# pressure.net
KiCad netlist of a schematic drawn in Altium Designer
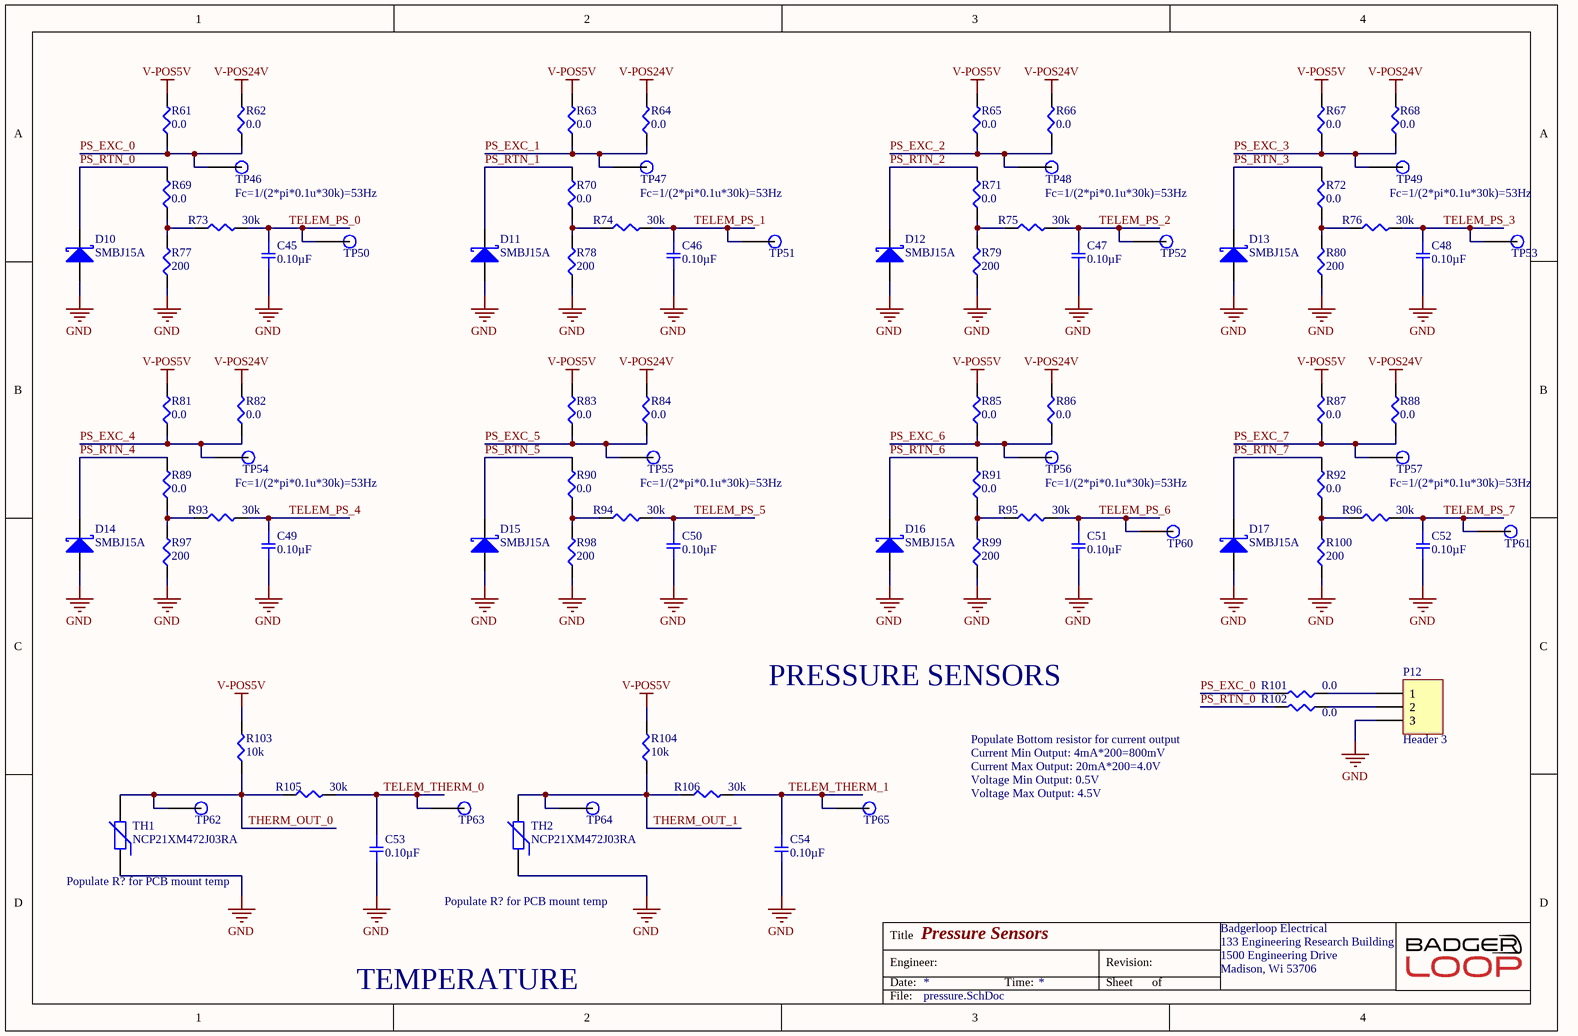
[diagram p0: pressure.SchDoc]

(export (version "E")
  (design (tool "Eeschema 10.0.6"))
  (components
    (comp (ref "C45")
      (value "0.10µF")
      (footprint "SMD-0805C")
      (description "CAP CER 0.1UF 25V X7R 0805")
      (fields
        (field (name "DIGI-KEY PART NUMBER") "490-12754-1-ND")
        (field (name "PART NUMBER") "GRM219R71E104KA01D")
      )
      (libsource (lib "capacitors") (part "GRM219R71E104KA01D"))
    )
    (comp (ref "C46")
      (value "0.10µF")
      (footprint "SMD-0805C")
      (description "CAP CER 0.1UF 25V X7R 0805")
      (fields
        (field (name "DIGI-KEY PART NUMBER") "490-12754-1-ND")
        (field (name "PART NUMBER") "GRM219R71E104KA01D")
      )
      (libsource (lib "capacitors") (part "GRM219R71E104KA01D"))
    )
    (comp (ref "C47")
      (value "0.10µF")
      (footprint "SMD-0805C")
      (description "CAP CER 0.1UF 25V X7R 0805")
      (fields
        (field (name "DIGI-KEY PART NUMBER") "490-12754-1-ND")
        (field (name "PART NUMBER") "GRM219R71E104KA01D")
      )
      (libsource (lib "capacitors") (part "GRM219R71E104KA01D"))
    )
    (comp (ref "C48")
      (value "0.10µF")
      (footprint "SMD-0805C")
      (description "CAP CER 0.1UF 25V X7R 0805")
      (fields
        (field (name "DIGI-KEY PART NUMBER") "490-12754-1-ND")
        (field (name "PART NUMBER") "GRM219R71E104KA01D")
      )
      (libsource (lib "capacitors") (part "GRM219R71E104KA01D"))
    )
    (comp (ref "C49")
      (value "0.10µF")
      (footprint "SMD-0805C")
      (description "CAP CER 0.1UF 25V X7R 0805")
      (fields
        (field (name "DIGI-KEY PART NUMBER") "490-12754-1-ND")
        (field (name "PART NUMBER") "GRM219R71E104KA01D")
      )
      (libsource (lib "capacitors") (part "GRM219R71E104KA01D"))
    )
    (comp (ref "C50")
      (value "0.10µF")
      (footprint "SMD-0805C")
      (description "CAP CER 0.1UF 25V X7R 0805")
      (fields
        (field (name "DIGI-KEY PART NUMBER") "490-12754-1-ND")
        (field (name "PART NUMBER") "GRM219R71E104KA01D")
      )
      (libsource (lib "capacitors") (part "GRM219R71E104KA01D"))
    )
    (comp (ref "C51")
      (value "0.10µF")
      (footprint "SMD-0805C")
      (description "CAP CER 0.1UF 25V X7R 0805")
      (fields
        (field (name "DIGI-KEY PART NUMBER") "490-12754-1-ND")
        (field (name "PART NUMBER") "GRM219R71E104KA01D")
      )
      (libsource (lib "capacitors") (part "GRM219R71E104KA01D"))
    )
    (comp (ref "C52")
      (value "0.10µF")
      (footprint "SMD-0805C")
      (description "CAP CER 0.1UF 25V X7R 0805")
      (fields
        (field (name "DIGI-KEY PART NUMBER") "490-12754-1-ND")
        (field (name "PART NUMBER") "GRM219R71E104KA01D")
      )
      (libsource (lib "capacitors") (part "GRM219R71E104KA01D"))
    )
    (comp (ref "C53")
      (value "0.10µF")
      (footprint "SMD-0805C")
      (description "CAP CER 0.1UF 16V X7R 0805")
      (fields
        (field (name "DIGI-KEY PART NUMBER") "490-1683-1-ND")
        (field (name "PART NUMBER") "GRM219R71C104KA01D")
      )
      (libsource (lib "capacitors") (part "GRM219R71C104KA01D"))
    )
    (comp (ref "C54")
      (value "0.10µF")
      (footprint "SMD-0805C")
      (description "CAP CER 0.1UF 16V X7R 0805")
      (fields
        (field (name "DIGI-KEY PART NUMBER") "490-1683-1-ND")
        (field (name "PART NUMBER") "GRM219R71C104KA01D")
      )
      (libsource (lib "capacitors") (part "GRM219R71C104KA01D"))
    )
    (comp (ref "D10")
      (value "SMBJ15A")
      (footprint "DIOM4436X26N")
      (description "TVS DIODE 15V 24.4V DO214AA")
      (fields (field (name "MANUFACTURER") "Littelfuse") (field (name "VOLTAGE") "5V"))
      (libsource (lib "misc") (part "SMBJ15A"))
    )
    (comp (ref "D11")
      (value "SMBJ15A")
      (footprint "DIOM4436X26N")
      (description "TVS DIODE 15V 24.4V DO214AA")
      (fields (field (name "MANUFACTURER") "Littelfuse") (field (name "VOLTAGE") "5V"))
      (libsource (lib "misc") (part "SMBJ15A"))
    )
    (comp (ref "D12")
      (value "SMBJ15A")
      (footprint "DIOM4436X26N")
      (description "TVS DIODE 15V 24.4V DO214AA")
      (fields (field (name "MANUFACTURER") "Littelfuse") (field (name "VOLTAGE") "5V"))
      (libsource (lib "misc") (part "SMBJ15A"))
    )
    (comp (ref "D13")
      (value "SMBJ15A")
      (footprint "DIOM4436X26N")
      (description "TVS DIODE 15V 24.4V DO214AA")
      (fields (field (name "MANUFACTURER") "Littelfuse") (field (name "VOLTAGE") "5V"))
      (libsource (lib "misc") (part "SMBJ15A"))
    )
    (comp (ref "D14")
      (value "SMBJ15A")
      (footprint "DIOM4436X26N")
      (description "TVS DIODE 15V 24.4V DO214AA")
      (fields (field (name "MANUFACTURER") "Littelfuse") (field (name "VOLTAGE") "5V"))
      (libsource (lib "misc") (part "SMBJ15A"))
    )
    (comp (ref "D15")
      (value "SMBJ15A")
      (footprint "DIOM4436X26N")
      (description "TVS DIODE 15V 24.4V DO214AA")
      (fields (field (name "MANUFACTURER") "Littelfuse") (field (name "VOLTAGE") "5V"))
      (libsource (lib "misc") (part "SMBJ15A"))
    )
    (comp (ref "D16")
      (value "SMBJ15A")
      (footprint "DIOM4436X26N")
      (description "TVS DIODE 15V 24.4V DO214AA")
      (fields (field (name "MANUFACTURER") "Littelfuse") (field (name "VOLTAGE") "5V"))
      (libsource (lib "misc") (part "SMBJ15A"))
    )
    (comp (ref "D17")
      (value "SMBJ15A")
      (footprint "DIOM4436X26N")
      (description "TVS DIODE 15V 24.4V DO214AA")
      (fields (field (name "MANUFACTURER") "Littelfuse") (field (name "VOLTAGE") "5V"))
      (libsource (lib "misc") (part "SMBJ15A"))
    )
    (comp (ref "P12")
      (value "Header 3")
      (footprint "Pin Header 1x3 TH Pitch 2.54mm")
      (description "Header, 3-Pin")
      (fields (field (name "PUBLISHER") "Altium Limited"))
      (libsource (lib "connector") (part "Header 3"))
    )
    (comp (ref "R61")
      (value "0.0")
      (footprint "SMD-0805-RES")
      (description "RES SMD 0.0 OHM JUMPER 1/8W 0805")
      (fields (field (name "PART NUMBER") "ERJ-6GEY0R00V") (field (name "DIGI-KEY PART NUMBER") "P0.0ACT-ND"))
      (libsource (lib "resistors") (part "ERJ-6GEY0R00V"))
    )
    (comp (ref "R62")
      (value "0.0")
      (footprint "SMD-0805-RES")
      (description "RES SMD 0.0 OHM JUMPER 1/8W 0805")
      (fields (field (name "PART NUMBER") "ERJ-6GEY0R00V") (field (name "DIGI-KEY PART NUMBER") "P0.0ACT-ND"))
      (libsource (lib "resistors") (part "ERJ-6GEY0R00V"))
    )
    (comp (ref "R63")
      (value "0.0")
      (footprint "SMD-0805-RES")
      (description "RES SMD 0.0 OHM JUMPER 1/8W 0805")
      (fields (field (name "PART NUMBER") "ERJ-6GEY0R00V") (field (name "DIGI-KEY PART NUMBER") "P0.0ACT-ND"))
      (libsource (lib "resistors") (part "ERJ-6GEY0R00V"))
    )
    (comp (ref "R64")
      (value "0.0")
      (footprint "SMD-0805-RES")
      (description "RES SMD 0.0 OHM JUMPER 1/8W 0805")
      (fields (field (name "PART NUMBER") "ERJ-6GEY0R00V") (field (name "DIGI-KEY PART NUMBER") "P0.0ACT-ND"))
      (libsource (lib "resistors") (part "ERJ-6GEY0R00V"))
    )
    (comp (ref "R65")
      (value "0.0")
      (footprint "SMD-0805-RES")
      (description "RES SMD 0.0 OHM JUMPER 1/8W 0805")
      (fields (field (name "PART NUMBER") "ERJ-6GEY0R00V") (field (name "DIGI-KEY PART NUMBER") "P0.0ACT-ND"))
      (libsource (lib "resistors") (part "ERJ-6GEY0R00V"))
    )
    (comp (ref "R66")
      (value "0.0")
      (footprint "SMD-0805-RES")
      (description "RES SMD 0.0 OHM JUMPER 1/8W 0805")
      (fields (field (name "PART NUMBER") "ERJ-6GEY0R00V") (field (name "DIGI-KEY PART NUMBER") "P0.0ACT-ND"))
      (libsource (lib "resistors") (part "ERJ-6GEY0R00V"))
    )
    (comp (ref "R67")
      (value "0.0")
      (footprint "SMD-0805-RES")
      (description "RES SMD 0.0 OHM JUMPER 1/8W 0805")
      (fields (field (name "PART NUMBER") "ERJ-6GEY0R00V") (field (name "DIGI-KEY PART NUMBER") "P0.0ACT-ND"))
      (libsource (lib "resistors") (part "ERJ-6GEY0R00V"))
    )
    (comp (ref "R68")
      (value "0.0")
      (footprint "SMD-0805-RES")
      (description "RES SMD 0.0 OHM JUMPER 1/8W 0805")
      (fields (field (name "PART NUMBER") "ERJ-6GEY0R00V") (field (name "DIGI-KEY PART NUMBER") "P0.0ACT-ND"))
      (libsource (lib "resistors") (part "ERJ-6GEY0R00V"))
    )
    (comp (ref "R69")
      (value "0.0")
      (footprint "SMD-0805-RES")
      (description "RES SMD 0.0 OHM JUMPER 1/8W 0805")
      (fields (field (name "PART NUMBER") "ERJ-6GEY0R00V") (field (name "DIGI-KEY PART NUMBER") "P0.0ACT-ND"))
      (libsource (lib "resistors") (part "ERJ-6GEY0R00V"))
    )
    (comp (ref "R70")
      (value "0.0")
      (footprint "SMD-0805-RES")
      (description "RES SMD 0.0 OHM JUMPER 1/8W 0805")
      (fields (field (name "PART NUMBER") "ERJ-6GEY0R00V") (field (name "DIGI-KEY PART NUMBER") "P0.0ACT-ND"))
      (libsource (lib "resistors") (part "ERJ-6GEY0R00V"))
    )
    (comp (ref "R71")
      (value "0.0")
      (footprint "SMD-0805-RES")
      (description "RES SMD 0.0 OHM JUMPER 1/8W 0805")
      (fields (field (name "PART NUMBER") "ERJ-6GEY0R00V") (field (name "DIGI-KEY PART NUMBER") "P0.0ACT-ND"))
      (libsource (lib "resistors") (part "ERJ-6GEY0R00V"))
    )
    (comp (ref "R72")
      (value "0.0")
      (footprint "SMD-0805-RES")
      (description "RES SMD 0.0 OHM JUMPER 1/8W 0805")
      (fields (field (name "PART NUMBER") "ERJ-6GEY0R00V") (field (name "DIGI-KEY PART NUMBER") "P0.0ACT-ND"))
      (libsource (lib "resistors") (part "ERJ-6GEY0R00V"))
    )
    (comp (ref "R73")
      (value "30k")
      (footprint "SMD-0805-RES")
      (description "RES SMD 30K OHM 1% 1/8W 0805")
      (fields
        (field (name "PART NUMBER") "ERJ-6ENF3002V")
        (field (name "DIGI-KEY PART NUMBER") "P30.0KCCT-ND")
      )
      (libsource (lib "resistors") (part "ERJ-6ENF3002V"))
    )
    (comp (ref "R74")
      (value "30k")
      (footprint "SMD-0805-RES")
      (description "RES SMD 30K OHM 1% 1/8W 0805")
      (fields
        (field (name "PART NUMBER") "ERJ-6ENF3002V")
        (field (name "DIGI-KEY PART NUMBER") "P30.0KCCT-ND")
      )
      (libsource (lib "resistors") (part "ERJ-6ENF3002V"))
    )
    (comp (ref "R75")
      (value "30k")
      (footprint "SMD-0805-RES")
      (description "RES SMD 30K OHM 1% 1/8W 0805")
      (fields
        (field (name "PART NUMBER") "ERJ-6ENF3002V")
        (field (name "DIGI-KEY PART NUMBER") "P30.0KCCT-ND")
      )
      (libsource (lib "resistors") (part "ERJ-6ENF3002V"))
    )
    (comp (ref "R76")
      (value "30k")
      (footprint "SMD-0805-RES")
      (description "RES SMD 30K OHM 1% 1/8W 0805")
      (fields
        (field (name "PART NUMBER") "ERJ-6ENF3002V")
        (field (name "DIGI-KEY PART NUMBER") "P30.0KCCT-ND")
      )
      (libsource (lib "resistors") (part "ERJ-6ENF3002V"))
    )
    (comp (ref "R77")
      (value "200")
      (footprint "SMD-0805-RES")
      (description "RES SMD 200 OHM 1% 1/2W 0805")
      (fields
        (field (name "PART NUMBER") "ERJ-P06F2000V")
        (field (name "DIGI-KEY PART NUMBER") "P16064CT-ND")
      )
      (libsource (lib "resistors") (part "ERJ-P06F2000V"))
    )
    (comp (ref "R78")
      (value "200")
      (footprint "SMD-0805-RES")
      (description "RES SMD 200 OHM 1% 1/2W 0805")
      (fields
        (field (name "PART NUMBER") "ERJ-P06F2000V")
        (field (name "DIGI-KEY PART NUMBER") "P16064CT-ND")
      )
      (libsource (lib "resistors") (part "ERJ-P06F2000V"))
    )
    (comp (ref "R79")
      (value "200")
      (footprint "SMD-0805-RES")
      (description "RES SMD 200 OHM 1% 1/2W 0805")
      (fields
        (field (name "PART NUMBER") "ERJ-P06F2000V")
        (field (name "DIGI-KEY PART NUMBER") "P16064CT-ND")
      )
      (libsource (lib "resistors") (part "ERJ-P06F2000V"))
    )
    (comp (ref "R80")
      (value "200")
      (footprint "SMD-0805-RES")
      (description "RES SMD 200 OHM 1% 1/2W 0805")
      (fields
        (field (name "PART NUMBER") "ERJ-P06F2000V")
        (field (name "DIGI-KEY PART NUMBER") "P16064CT-ND")
      )
      (libsource (lib "resistors") (part "ERJ-P06F2000V"))
    )
    (comp (ref "R81")
      (value "0.0")
      (footprint "SMD-0805-RES")
      (description "RES SMD 0.0 OHM JUMPER 1/8W 0805")
      (fields (field (name "PART NUMBER") "ERJ-6GEY0R00V") (field (name "DIGI-KEY PART NUMBER") "P0.0ACT-ND"))
      (libsource (lib "resistors") (part "ERJ-6GEY0R00V"))
    )
    (comp (ref "R82")
      (value "0.0")
      (footprint "SMD-0805-RES")
      (description "RES SMD 0.0 OHM JUMPER 1/8W 0805")
      (fields (field (name "PART NUMBER") "ERJ-6GEY0R00V") (field (name "DIGI-KEY PART NUMBER") "P0.0ACT-ND"))
      (libsource (lib "resistors") (part "ERJ-6GEY0R00V"))
    )
    (comp (ref "R83")
      (value "0.0")
      (footprint "SMD-0805-RES")
      (description "RES SMD 0.0 OHM JUMPER 1/8W 0805")
      (fields (field (name "PART NUMBER") "ERJ-6GEY0R00V") (field (name "DIGI-KEY PART NUMBER") "P0.0ACT-ND"))
      (libsource (lib "resistors") (part "ERJ-6GEY0R00V"))
    )
    (comp (ref "R84")
      (value "0.0")
      (footprint "SMD-0805-RES")
      (description "RES SMD 0.0 OHM JUMPER 1/8W 0805")
      (fields (field (name "PART NUMBER") "ERJ-6GEY0R00V") (field (name "DIGI-KEY PART NUMBER") "P0.0ACT-ND"))
      (libsource (lib "resistors") (part "ERJ-6GEY0R00V"))
    )
    (comp (ref "R85")
      (value "0.0")
      (footprint "SMD-0805-RES")
      (description "RES SMD 0.0 OHM JUMPER 1/8W 0805")
      (fields (field (name "PART NUMBER") "ERJ-6GEY0R00V") (field (name "DIGI-KEY PART NUMBER") "P0.0ACT-ND"))
      (libsource (lib "resistors") (part "ERJ-6GEY0R00V"))
    )
    (comp (ref "R86")
      (value "0.0")
      (footprint "SMD-0805-RES")
      (description "RES SMD 0.0 OHM JUMPER 1/8W 0805")
      (fields (field (name "PART NUMBER") "ERJ-6GEY0R00V") (field (name "DIGI-KEY PART NUMBER") "P0.0ACT-ND"))
      (libsource (lib "resistors") (part "ERJ-6GEY0R00V"))
    )
    (comp (ref "R87")
      (value "0.0")
      (footprint "SMD-0805-RES")
      (description "RES SMD 0.0 OHM JUMPER 1/8W 0805")
      (fields (field (name "PART NUMBER") "ERJ-6GEY0R00V") (field (name "DIGI-KEY PART NUMBER") "P0.0ACT-ND"))
      (libsource (lib "resistors") (part "ERJ-6GEY0R00V"))
    )
    (comp (ref "R88")
      (value "0.0")
      (footprint "SMD-0805-RES")
      (description "RES SMD 0.0 OHM JUMPER 1/8W 0805")
      (fields (field (name "PART NUMBER") "ERJ-6GEY0R00V") (field (name "DIGI-KEY PART NUMBER") "P0.0ACT-ND"))
      (libsource (lib "resistors") (part "ERJ-6GEY0R00V"))
    )
    (comp (ref "R89")
      (value "0.0")
      (footprint "SMD-0805-RES")
      (description "RES SMD 0.0 OHM JUMPER 1/8W 0805")
      (fields (field (name "PART NUMBER") "ERJ-6GEY0R00V") (field (name "DIGI-KEY PART NUMBER") "P0.0ACT-ND"))
      (libsource (lib "resistors") (part "ERJ-6GEY0R00V"))
    )
    (comp (ref "R90")
      (value "0.0")
      (footprint "SMD-0805-RES")
      (description "RES SMD 0.0 OHM JUMPER 1/8W 0805")
      (fields (field (name "PART NUMBER") "ERJ-6GEY0R00V") (field (name "DIGI-KEY PART NUMBER") "P0.0ACT-ND"))
      (libsource (lib "resistors") (part "ERJ-6GEY0R00V"))
    )
    (comp (ref "R91")
      (value "0.0")
      (footprint "SMD-0805-RES")
      (description "RES SMD 0.0 OHM JUMPER 1/8W 0805")
      (fields (field (name "PART NUMBER") "ERJ-6GEY0R00V") (field (name "DIGI-KEY PART NUMBER") "P0.0ACT-ND"))
      (libsource (lib "resistors") (part "ERJ-6GEY0R00V"))
    )
    (comp (ref "R92")
      (value "0.0")
      (footprint "SMD-0805-RES")
      (description "RES SMD 0.0 OHM JUMPER 1/8W 0805")
      (fields (field (name "PART NUMBER") "ERJ-6GEY0R00V") (field (name "DIGI-KEY PART NUMBER") "P0.0ACT-ND"))
      (libsource (lib "resistors") (part "ERJ-6GEY0R00V"))
    )
    (comp (ref "R93")
      (value "30k")
      (footprint "SMD-0805-RES")
      (description "RES SMD 30K OHM 1% 1/8W 0805")
      (fields
        (field (name "PART NUMBER") "ERJ-6ENF3002V")
        (field (name "DIGI-KEY PART NUMBER") "P30.0KCCT-ND")
      )
      (libsource (lib "resistors") (part "ERJ-6ENF3002V"))
    )
    (comp (ref "R94")
      (value "30k")
      (footprint "SMD-0805-RES")
      (description "RES SMD 30K OHM 1% 1/8W 0805")
      (fields
        (field (name "PART NUMBER") "ERJ-6ENF3002V")
        (field (name "DIGI-KEY PART NUMBER") "P30.0KCCT-ND")
      )
      (libsource (lib "resistors") (part "ERJ-6ENF3002V"))
    )
    (comp (ref "R95")
      (value "30k")
      (footprint "SMD-0805-RES")
      (description "RES SMD 30K OHM 1% 1/8W 0805")
      (fields
        (field (name "PART NUMBER") "ERJ-6ENF3002V")
        (field (name "DIGI-KEY PART NUMBER") "P30.0KCCT-ND")
      )
      (libsource (lib "resistors") (part "ERJ-6ENF3002V"))
    )
    (comp (ref "R96")
      (value "30k")
      (footprint "SMD-0805-RES")
      (description "RES SMD 30K OHM 1% 1/8W 0805")
      (fields
        (field (name "PART NUMBER") "ERJ-6ENF3002V")
        (field (name "DIGI-KEY PART NUMBER") "P30.0KCCT-ND")
      )
      (libsource (lib "resistors") (part "ERJ-6ENF3002V"))
    )
    (comp (ref "R97")
      (value "200")
      (footprint "SMD-0805-RES")
      (description "RES SMD 200 OHM 1% 1/2W 0805")
      (fields
        (field (name "PART NUMBER") "ERJ-P06F2000V")
        (field (name "DIGI-KEY PART NUMBER") "P16064CT-ND")
      )
      (libsource (lib "resistors") (part "ERJ-P06F2000V"))
    )
    (comp (ref "R98")
      (value "200")
      (footprint "SMD-0805-RES")
      (description "RES SMD 200 OHM 1% 1/2W 0805")
      (fields
        (field (name "PART NUMBER") "ERJ-P06F2000V")
        (field (name "DIGI-KEY PART NUMBER") "P16064CT-ND")
      )
      (libsource (lib "resistors") (part "ERJ-P06F2000V"))
    )
    (comp (ref "R99")
      (value "200")
      (footprint "SMD-0805-RES")
      (description "RES SMD 200 OHM 1% 1/2W 0805")
      (fields
        (field (name "PART NUMBER") "ERJ-P06F2000V")
        (field (name "DIGI-KEY PART NUMBER") "P16064CT-ND")
      )
      (libsource (lib "resistors") (part "ERJ-P06F2000V"))
    )
    (comp (ref "R100")
      (value "200")
      (footprint "SMD-0805-RES")
      (description "RES SMD 200 OHM 1% 1/2W 0805")
      (fields
        (field (name "PART NUMBER") "ERJ-P06F2000V")
        (field (name "DIGI-KEY PART NUMBER") "P16064CT-ND")
      )
      (libsource (lib "resistors") (part "ERJ-P06F2000V"))
    )
    (comp (ref "R101")
      (value "0.0")
      (footprint "SMD-0805-RES")
      (description "RES SMD 0.0 OHM JUMPER 1/8W 0805")
      (fields (field (name "PART NUMBER") "ERJ-6GEY0R00V") (field (name "DIGI-KEY PART NUMBER") "P0.0ACT-ND"))
      (libsource (lib "resistors") (part "ERJ-6GEY0R00V"))
    )
    (comp (ref "R102")
      (value "0.0")
      (footprint "SMD-0805-RES")
      (description "RES SMD 0.0 OHM JUMPER 1/8W 0805")
      (fields (field (name "PART NUMBER") "ERJ-6GEY0R00V") (field (name "DIGI-KEY PART NUMBER") "P0.0ACT-ND"))
      (libsource (lib "resistors") (part "ERJ-6GEY0R00V"))
    )
    (comp (ref "R103")
      (value "10k")
      (footprint "SMD-0805-RES")
      (description "RES SMD 10K OHM 1% 1/2W 0805")
      (fields
        (field (name "PART NUMBER") "ERJ-P06F1002V")
        (field (name "DIGI-KEY PART NUMBER") "P16059CT-ND")
      )
      (libsource (lib "resistors") (part "ERJ-P06F1002V"))
    )
    (comp (ref "R104")
      (value "10k")
      (footprint "SMD-0805-RES")
      (description "RES SMD 10K OHM 1% 1/2W 0805")
      (fields
        (field (name "PART NUMBER") "ERJ-P06F1002V")
        (field (name "DIGI-KEY PART NUMBER") "P16059CT-ND")
      )
      (libsource (lib "resistors") (part "ERJ-P06F1002V"))
    )
    (comp (ref "R105")
      (value "30k")
      (footprint "SMD-0805-RES")
      (description "RES SMD 30K OHM 1% 1/8W 0805")
      (fields
        (field (name "PART NUMBER") "ERJ-6ENF3002V")
        (field (name "DIGI-KEY PART NUMBER") "P30.0KCCT-ND")
      )
      (libsource (lib "resistors") (part "ERJ-6ENF3002V"))
    )
    (comp (ref "R106")
      (value "30k")
      (footprint "SMD-0805-RES")
      (description "RES SMD 30K OHM 1% 1/8W 0805")
      (fields
        (field (name "PART NUMBER") "ERJ-6ENF3002V")
        (field (name "DIGI-KEY PART NUMBER") "P30.0KCCT-ND")
      )
      (libsource (lib "resistors") (part "ERJ-6ENF3002V"))
    )
    (comp (ref "TH1")
      (value "NCP21XM472J03RA")
      (footprint "SMD-0805-RES")
      (description "NTC THERMISTOR 4.7K OHM 5% 0805")
      (fields (field (name "MANUFACTURER") "Murata") (field (name "TOLERANCE") "5%"))
      (libsource (lib "misc") (part "NCP21XM472J03RA"))
    )
    (comp (ref "TH2")
      (value "NCP21XM472J03RA")
      (footprint "SMD-0805-RES")
      (description "NTC THERMISTOR 4.7K OHM 5% 0805")
      (fields (field (name "MANUFACTURER") "Murata") (field (name "TOLERANCE") "5%"))
      (libsource (lib "misc") (part "NCP21XM472J03RA"))
    )
    (comp (ref "TP46")
      (value "TP")
      (footprint "Test Point")
      (description "SMD TEST POINT")
      (libsource (lib "misc") (part "TP"))
    )
    (comp (ref "TP47")
      (value "TP")
      (footprint "Test Point")
      (description "SMD TEST POINT")
      (libsource (lib "misc") (part "TP"))
    )
    (comp (ref "TP48")
      (value "TP")
      (footprint "Test Point")
      (description "SMD TEST POINT")
      (libsource (lib "misc") (part "TP"))
    )
    (comp (ref "TP49")
      (value "TP")
      (footprint "Test Point")
      (description "SMD TEST POINT")
      (libsource (lib "misc") (part "TP"))
    )
    (comp (ref "TP50")
      (value "TP")
      (footprint "Test Point")
      (description "SMD TEST POINT")
      (libsource (lib "misc") (part "TP"))
    )
    (comp (ref "TP51")
      (value "TP")
      (footprint "Test Point")
      (description "SMD TEST POINT")
      (libsource (lib "misc") (part "TP"))
    )
    (comp (ref "TP52")
      (value "TP")
      (footprint "Test Point")
      (description "SMD TEST POINT")
      (libsource (lib "misc") (part "TP"))
    )
    (comp (ref "TP53")
      (value "TP")
      (footprint "Test Point")
      (description "SMD TEST POINT")
      (libsource (lib "misc") (part "TP"))
    )
    (comp (ref "TP54")
      (value "TP")
      (footprint "Test Point")
      (description "SMD TEST POINT")
      (libsource (lib "misc") (part "TP"))
    )
    (comp (ref "TP55")
      (value "TP")
      (footprint "Test Point")
      (description "SMD TEST POINT")
      (libsource (lib "misc") (part "TP"))
    )
    (comp (ref "TP56")
      (value "TP")
      (footprint "Test Point")
      (description "SMD TEST POINT")
      (libsource (lib "misc") (part "TP"))
    )
    (comp (ref "TP57")
      (value "TP")
      (footprint "Test Point")
      (description "SMD TEST POINT")
      (libsource (lib "misc") (part "TP"))
    )
    (comp (ref "TP60")
      (value "TP")
      (footprint "Test Point")
      (description "SMD TEST POINT")
      (libsource (lib "misc") (part "TP"))
    )
    (comp (ref "TP61")
      (value "TP")
      (footprint "Test Point")
      (description "SMD TEST POINT")
      (libsource (lib "misc") (part "TP"))
    )
    (comp (ref "TP62")
      (value "TP")
      (footprint "Test Point")
      (description "SMD TEST POINT")
      (libsource (lib "misc") (part "TP"))
    )
    (comp (ref "TP63")
      (value "TP")
      (footprint "Test Point")
      (description "SMD TEST POINT")
      (libsource (lib "misc") (part "TP"))
    )
    (comp (ref "TP64")
      (value "TP")
      (footprint "Test Point")
      (description "SMD TEST POINT")
      (libsource (lib "misc") (part "TP"))
    )
    (comp (ref "TP65")
      (value "TP")
      (footprint "Test Point")
      (description "SMD TEST POINT")
      (libsource (lib "misc") (part "TP"))
    )
  )
  (nets
    (net (code "1") (name "/PS_EXC_0") (class "Default")
      (node (ref "R101") (pin "2") (pinfunction "2_2") (pintype "passive"))
      (node (ref "R61") (pin "1") (pinfunction "1_1") (pintype "passive"))
      (node (ref "R62") (pin "1") (pinfunction "1_1") (pintype "passive"))
      (node (ref "TP46") (pin "1") (pinfunction "1_1") (pintype "passive"))
    )
    (net (code "2") (name "/PS_EXC_1") (class "Default")
      (node (ref "R63") (pin "1") (pinfunction "1_1") (pintype "passive"))
      (node (ref "R64") (pin "1") (pinfunction "1_1") (pintype "passive"))
      (node (ref "TP47") (pin "1") (pinfunction "1_1") (pintype "passive"))
    )
    (net (code "3") (name "/PS_EXC_2") (class "Default")
      (node (ref "R65") (pin "1") (pinfunction "1_1") (pintype "passive"))
      (node (ref "R66") (pin "1") (pinfunction "1_1") (pintype "passive"))
      (node (ref "TP48") (pin "1") (pinfunction "1_1") (pintype "passive"))
    )
    (net (code "4") (name "/PS_EXC_3") (class "Default")
      (node (ref "R67") (pin "1") (pinfunction "1_1") (pintype "passive"))
      (node (ref "R68") (pin "1") (pinfunction "1_1") (pintype "passive"))
      (node (ref "TP49") (pin "1") (pinfunction "1_1") (pintype "passive"))
    )
    (net (code "5") (name "/PS_EXC_4") (class "Default")
      (node (ref "R81") (pin "1") (pinfunction "1_1") (pintype "passive"))
      (node (ref "R82") (pin "1") (pinfunction "1_1") (pintype "passive"))
      (node (ref "TP54") (pin "1") (pinfunction "1_1") (pintype "passive"))
    )
    (net (code "6") (name "/PS_EXC_5") (class "Default")
      (node (ref "R83") (pin "1") (pinfunction "1_1") (pintype "passive"))
      (node (ref "R84") (pin "1") (pinfunction "1_1") (pintype "passive"))
      (node (ref "TP55") (pin "1") (pinfunction "1_1") (pintype "passive"))
    )
    (net (code "7") (name "/PS_EXC_6") (class "Default")
      (node (ref "R85") (pin "1") (pinfunction "1_1") (pintype "passive"))
      (node (ref "R86") (pin "1") (pinfunction "1_1") (pintype "passive"))
      (node (ref "TP56") (pin "1") (pinfunction "1_1") (pintype "passive"))
    )
    (net (code "8") (name "/PS_EXC_7") (class "Default")
      (node (ref "R87") (pin "1") (pinfunction "1_1") (pintype "passive"))
      (node (ref "R88") (pin "1") (pinfunction "1_1") (pintype "passive"))
      (node (ref "TP57") (pin "1") (pinfunction "1_1") (pintype "passive"))
    )
    (net (code "9") (name "/PS_RTN_0") (class "Default")
      (node (ref "D10") (pin "1") (pinfunction "A_1") (pintype "passive"))
      (node (ref "R102") (pin "2") (pinfunction "2_2") (pintype "passive"))
      (node (ref "R69") (pin "2") (pinfunction "2_2") (pintype "passive"))
    )
    (net (code "10") (name "/PS_RTN_1") (class "Default")
      (node (ref "D11") (pin "1") (pinfunction "A_1") (pintype "passive"))
      (node (ref "R70") (pin "2") (pinfunction "2_2") (pintype "passive"))
    )
    (net (code "11") (name "/PS_RTN_2") (class "Default")
      (node (ref "D12") (pin "1") (pinfunction "A_1") (pintype "passive"))
      (node (ref "R71") (pin "2") (pinfunction "2_2") (pintype "passive"))
    )
    (net (code "12") (name "/PS_RTN_3") (class "Default")
      (node (ref "D13") (pin "1") (pinfunction "A_1") (pintype "passive"))
      (node (ref "R72") (pin "2") (pinfunction "2_2") (pintype "passive"))
    )
    (net (code "13") (name "/PS_RTN_4") (class "Default")
      (node (ref "D14") (pin "1") (pinfunction "A_1") (pintype "passive"))
      (node (ref "R89") (pin "2") (pinfunction "2_2") (pintype "passive"))
    )
    (net (code "14") (name "/PS_RTN_5") (class "Default")
      (node (ref "D15") (pin "1") (pinfunction "A_1") (pintype "passive"))
      (node (ref "R90") (pin "2") (pinfunction "2_2") (pintype "passive"))
    )
    (net (code "15") (name "/PS_RTN_6") (class "Default")
      (node (ref "D16") (pin "1") (pinfunction "A_1") (pintype "passive"))
      (node (ref "R91") (pin "2") (pinfunction "2_2") (pintype "passive"))
    )
    (net (code "16") (name "/PS_RTN_7") (class "Default")
      (node (ref "D17") (pin "1") (pinfunction "A_1") (pintype "passive"))
      (node (ref "R92") (pin "2") (pinfunction "2_2") (pintype "passive"))
    )
    (net (code "17") (name "/TELEM_PS_0") (class "Default")
      (node (ref "C45") (pin "1") (pinfunction "1_1") (pintype "passive"))
      (node (ref "R73") (pin "2") (pinfunction "2_2") (pintype "passive"))
      (node (ref "TP50") (pin "1") (pinfunction "1_1") (pintype "passive"))
    )
    (net (code "18") (name "/TELEM_PS_1") (class "Default")
      (node (ref "C46") (pin "1") (pinfunction "1_1") (pintype "passive"))
      (node (ref "R74") (pin "2") (pinfunction "2_2") (pintype "passive"))
      (node (ref "TP51") (pin "1") (pinfunction "1_1") (pintype "passive"))
    )
    (net (code "19") (name "/TELEM_PS_2") (class "Default")
      (node (ref "C47") (pin "1") (pinfunction "1_1") (pintype "passive"))
      (node (ref "R75") (pin "2") (pinfunction "2_2") (pintype "passive"))
      (node (ref "TP52") (pin "1") (pinfunction "1_1") (pintype "passive"))
    )
    (net (code "20") (name "/TELEM_PS_3") (class "Default")
      (node (ref "C48") (pin "1") (pinfunction "1_1") (pintype "passive"))
      (node (ref "R76") (pin "2") (pinfunction "2_2") (pintype "passive"))
      (node (ref "TP53") (pin "1") (pinfunction "1_1") (pintype "passive"))
    )
    (net (code "21") (name "/TELEM_PS_4") (class "Default")
      (node (ref "C49") (pin "1") (pinfunction "1_1") (pintype "passive"))
      (node (ref "R93") (pin "2") (pinfunction "2_2") (pintype "passive"))
    )
    (net (code "22") (name "/TELEM_PS_5") (class "Default")
      (node (ref "C50") (pin "1") (pinfunction "1_1") (pintype "passive"))
      (node (ref "R94") (pin "2") (pinfunction "2_2") (pintype "passive"))
    )
    (net (code "23") (name "/TELEM_PS_6") (class "Default")
      (node (ref "C51") (pin "1") (pinfunction "1_1") (pintype "passive"))
      (node (ref "R95") (pin "2") (pinfunction "2_2") (pintype "passive"))
      (node (ref "TP60") (pin "1") (pinfunction "1_1") (pintype "passive"))
    )
    (net (code "24") (name "/TELEM_PS_7") (class "Default")
      (node (ref "C52") (pin "1") (pinfunction "1_1") (pintype "passive"))
      (node (ref "R96") (pin "2") (pinfunction "2_2") (pintype "passive"))
      (node (ref "TP61") (pin "1") (pinfunction "1_1") (pintype "passive"))
    )
    (net (code "25") (name "/TELEM_THERM_0") (class "Default")
      (node (ref "C53") (pin "1") (pinfunction "1_1") (pintype "passive"))
      (node (ref "R105") (pin "2") (pinfunction "2_2") (pintype "passive"))
      (node (ref "TP63") (pin "1") (pinfunction "1_1") (pintype "passive"))
    )
    (net (code "26") (name "/TELEM_THERM_1") (class "Default")
      (node (ref "C54") (pin "1") (pinfunction "1_1") (pintype "passive"))
      (node (ref "R106") (pin "2") (pinfunction "2_2") (pintype "passive"))
      (node (ref "TP65") (pin "1") (pinfunction "1_1") (pintype "passive"))
    )
    (net (code "27") (name "/THERM_OUT_0") (class "Default")
      (node (ref "R103") (pin "1") (pinfunction "1_1") (pintype "passive"))
      (node (ref "R105") (pin "1") (pinfunction "1_1") (pintype "passive"))
      (node (ref "TH1") (pin "2") (pinfunction "2_2") (pintype "passive"))
      (node (ref "TP62") (pin "1") (pinfunction "1_1") (pintype "passive"))
    )
    (net (code "28") (name "/THERM_OUT_1") (class "Default")
      (node (ref "R104") (pin "1") (pinfunction "1_1") (pintype "passive"))
      (node (ref "R106") (pin "1") (pinfunction "1_1") (pintype "passive"))
      (node (ref "TH2") (pin "2") (pinfunction "2_2") (pintype "passive"))
      (node (ref "TP64") (pin "1") (pinfunction "1_1") (pintype "passive"))
    )
    (net (code "29") (name "GND") (class "Default")
      (node (ref "C45") (pin "2") (pinfunction "2_2") (pintype "passive"))
      (node (ref "C46") (pin "2") (pinfunction "2_2") (pintype "passive"))
      (node (ref "C47") (pin "2") (pinfunction "2_2") (pintype "passive"))
      (node (ref "C48") (pin "2") (pinfunction "2_2") (pintype "passive"))
      (node (ref "C49") (pin "2") (pinfunction "2_2") (pintype "passive"))
      (node (ref "C50") (pin "2") (pinfunction "2_2") (pintype "passive"))
      (node (ref "C51") (pin "2") (pinfunction "2_2") (pintype "passive"))
      (node (ref "C52") (pin "2") (pinfunction "2_2") (pintype "passive"))
      (node (ref "C53") (pin "2") (pinfunction "2_2") (pintype "passive"))
      (node (ref "C54") (pin "2") (pinfunction "2_2") (pintype "passive"))
      (node (ref "D10") (pin "2") (pinfunction "K_2") (pintype "passive"))
      (node (ref "D11") (pin "2") (pinfunction "K_2") (pintype "passive"))
      (node (ref "D12") (pin "2") (pinfunction "K_2") (pintype "passive"))
      (node (ref "D13") (pin "2") (pinfunction "K_2") (pintype "passive"))
      (node (ref "D14") (pin "2") (pinfunction "K_2") (pintype "passive"))
      (node (ref "D15") (pin "2") (pinfunction "K_2") (pintype "passive"))
      (node (ref "D16") (pin "2") (pinfunction "K_2") (pintype "passive"))
      (node (ref "D17") (pin "2") (pinfunction "K_2") (pintype "passive"))
      (node (ref "P12") (pin "3") (pinfunction "3_3") (pintype "passive"))
      (node (ref "R100") (pin "1") (pinfunction "1_1") (pintype "passive"))
      (node (ref "R77") (pin "1") (pinfunction "1_1") (pintype "passive"))
      (node (ref "R78") (pin "1") (pinfunction "1_1") (pintype "passive"))
      (node (ref "R79") (pin "1") (pinfunction "1_1") (pintype "passive"))
      (node (ref "R80") (pin "1") (pinfunction "1_1") (pintype "passive"))
      (node (ref "R97") (pin "1") (pinfunction "1_1") (pintype "passive"))
      (node (ref "R98") (pin "1") (pinfunction "1_1") (pintype "passive"))
      (node (ref "R99") (pin "1") (pinfunction "1_1") (pintype "passive"))
      (node (ref "TH1") (pin "1") (pinfunction "1_1") (pintype "passive"))
      (node (ref "TH2") (pin "1") (pinfunction "1_1") (pintype "passive"))
    )
    (net (code "30") (name "Net-(P12-Pad1)") (class "Default")
      (node (ref "P12") (pin "1") (pinfunction "1_1") (pintype "passive"))
      (node (ref "R101") (pin "1") (pinfunction "1_1") (pintype "passive"))
    )
    (net (code "31") (name "Net-(P12-Pad2)") (class "Default")
      (node (ref "P12") (pin "2") (pinfunction "2_2") (pintype "passive"))
      (node (ref "R102") (pin "1") (pinfunction "1_1") (pintype "passive"))
    )
    (net (code "32") (name "Net-(R69-Pad1)") (class "Default")
      (node (ref "R69") (pin "1") (pinfunction "1_1") (pintype "passive"))
      (node (ref "R73") (pin "1") (pinfunction "1_1") (pintype "passive"))
      (node (ref "R77") (pin "2") (pinfunction "2_2") (pintype "passive"))
    )
    (net (code "33") (name "Net-(R70-Pad1)") (class "Default")
      (node (ref "R70") (pin "1") (pinfunction "1_1") (pintype "passive"))
      (node (ref "R74") (pin "1") (pinfunction "1_1") (pintype "passive"))
      (node (ref "R78") (pin "2") (pinfunction "2_2") (pintype "passive"))
    )
    (net (code "34") (name "Net-(R71-Pad1)") (class "Default")
      (node (ref "R71") (pin "1") (pinfunction "1_1") (pintype "passive"))
      (node (ref "R75") (pin "1") (pinfunction "1_1") (pintype "passive"))
      (node (ref "R79") (pin "2") (pinfunction "2_2") (pintype "passive"))
    )
    (net (code "35") (name "Net-(R72-Pad1)") (class "Default")
      (node (ref "R72") (pin "1") (pinfunction "1_1") (pintype "passive"))
      (node (ref "R76") (pin "1") (pinfunction "1_1") (pintype "passive"))
      (node (ref "R80") (pin "2") (pinfunction "2_2") (pintype "passive"))
    )
    (net (code "36") (name "Net-(R89-Pad1)") (class "Default")
      (node (ref "R89") (pin "1") (pinfunction "1_1") (pintype "passive"))
      (node (ref "R93") (pin "1") (pinfunction "1_1") (pintype "passive"))
      (node (ref "R97") (pin "2") (pinfunction "2_2") (pintype "passive"))
    )
    (net (code "37") (name "Net-(R90-Pad1)") (class "Default")
      (node (ref "R90") (pin "1") (pinfunction "1_1") (pintype "passive"))
      (node (ref "R94") (pin "1") (pinfunction "1_1") (pintype "passive"))
      (node (ref "R98") (pin "2") (pinfunction "2_2") (pintype "passive"))
    )
    (net (code "38") (name "Net-(R91-Pad1)") (class "Default")
      (node (ref "R91") (pin "1") (pinfunction "1_1") (pintype "passive"))
      (node (ref "R95") (pin "1") (pinfunction "1_1") (pintype "passive"))
      (node (ref "R99") (pin "2") (pinfunction "2_2") (pintype "passive"))
    )
    (net (code "39") (name "Net-(R100-Pad2)") (class "Default")
      (node (ref "R100") (pin "2") (pinfunction "2_2") (pintype "passive"))
      (node (ref "R92") (pin "1") (pinfunction "1_1") (pintype "passive"))
      (node (ref "R96") (pin "1") (pinfunction "1_1") (pintype "passive"))
    )
    (net (code "40") (name "V-POS5V") (class "Default")
      (node (ref "R103") (pin "2") (pinfunction "2_2") (pintype "passive"))
      (node (ref "R104") (pin "2") (pinfunction "2_2") (pintype "passive"))
      (node (ref "R61") (pin "2") (pinfunction "2_2") (pintype "passive"))
      (node (ref "R63") (pin "2") (pinfunction "2_2") (pintype "passive"))
      (node (ref "R65") (pin "2") (pinfunction "2_2") (pintype "passive"))
      (node (ref "R67") (pin "2") (pinfunction "2_2") (pintype "passive"))
      (node (ref "R81") (pin "2") (pinfunction "2_2") (pintype "passive"))
      (node (ref "R83") (pin "2") (pinfunction "2_2") (pintype "passive"))
      (node (ref "R85") (pin "2") (pinfunction "2_2") (pintype "passive"))
      (node (ref "R87") (pin "2") (pinfunction "2_2") (pintype "passive"))
    )
    (net (code "41") (name "V-POS24V") (class "Default")
      (node (ref "R62") (pin "2") (pinfunction "2_2") (pintype "passive"))
      (node (ref "R64") (pin "2") (pinfunction "2_2") (pintype "passive"))
      (node (ref "R66") (pin "2") (pinfunction "2_2") (pintype "passive"))
      (node (ref "R68") (pin "2") (pinfunction "2_2") (pintype "passive"))
      (node (ref "R82") (pin "2") (pinfunction "2_2") (pintype "passive"))
      (node (ref "R84") (pin "2") (pinfunction "2_2") (pintype "passive"))
      (node (ref "R86") (pin "2") (pinfunction "2_2") (pintype "passive"))
      (node (ref "R88") (pin "2") (pinfunction "2_2") (pintype "passive"))
    )
  )
)
